# quadESP_Mark_2.net
KiCad netlist of a schematic drawn in EAGLE
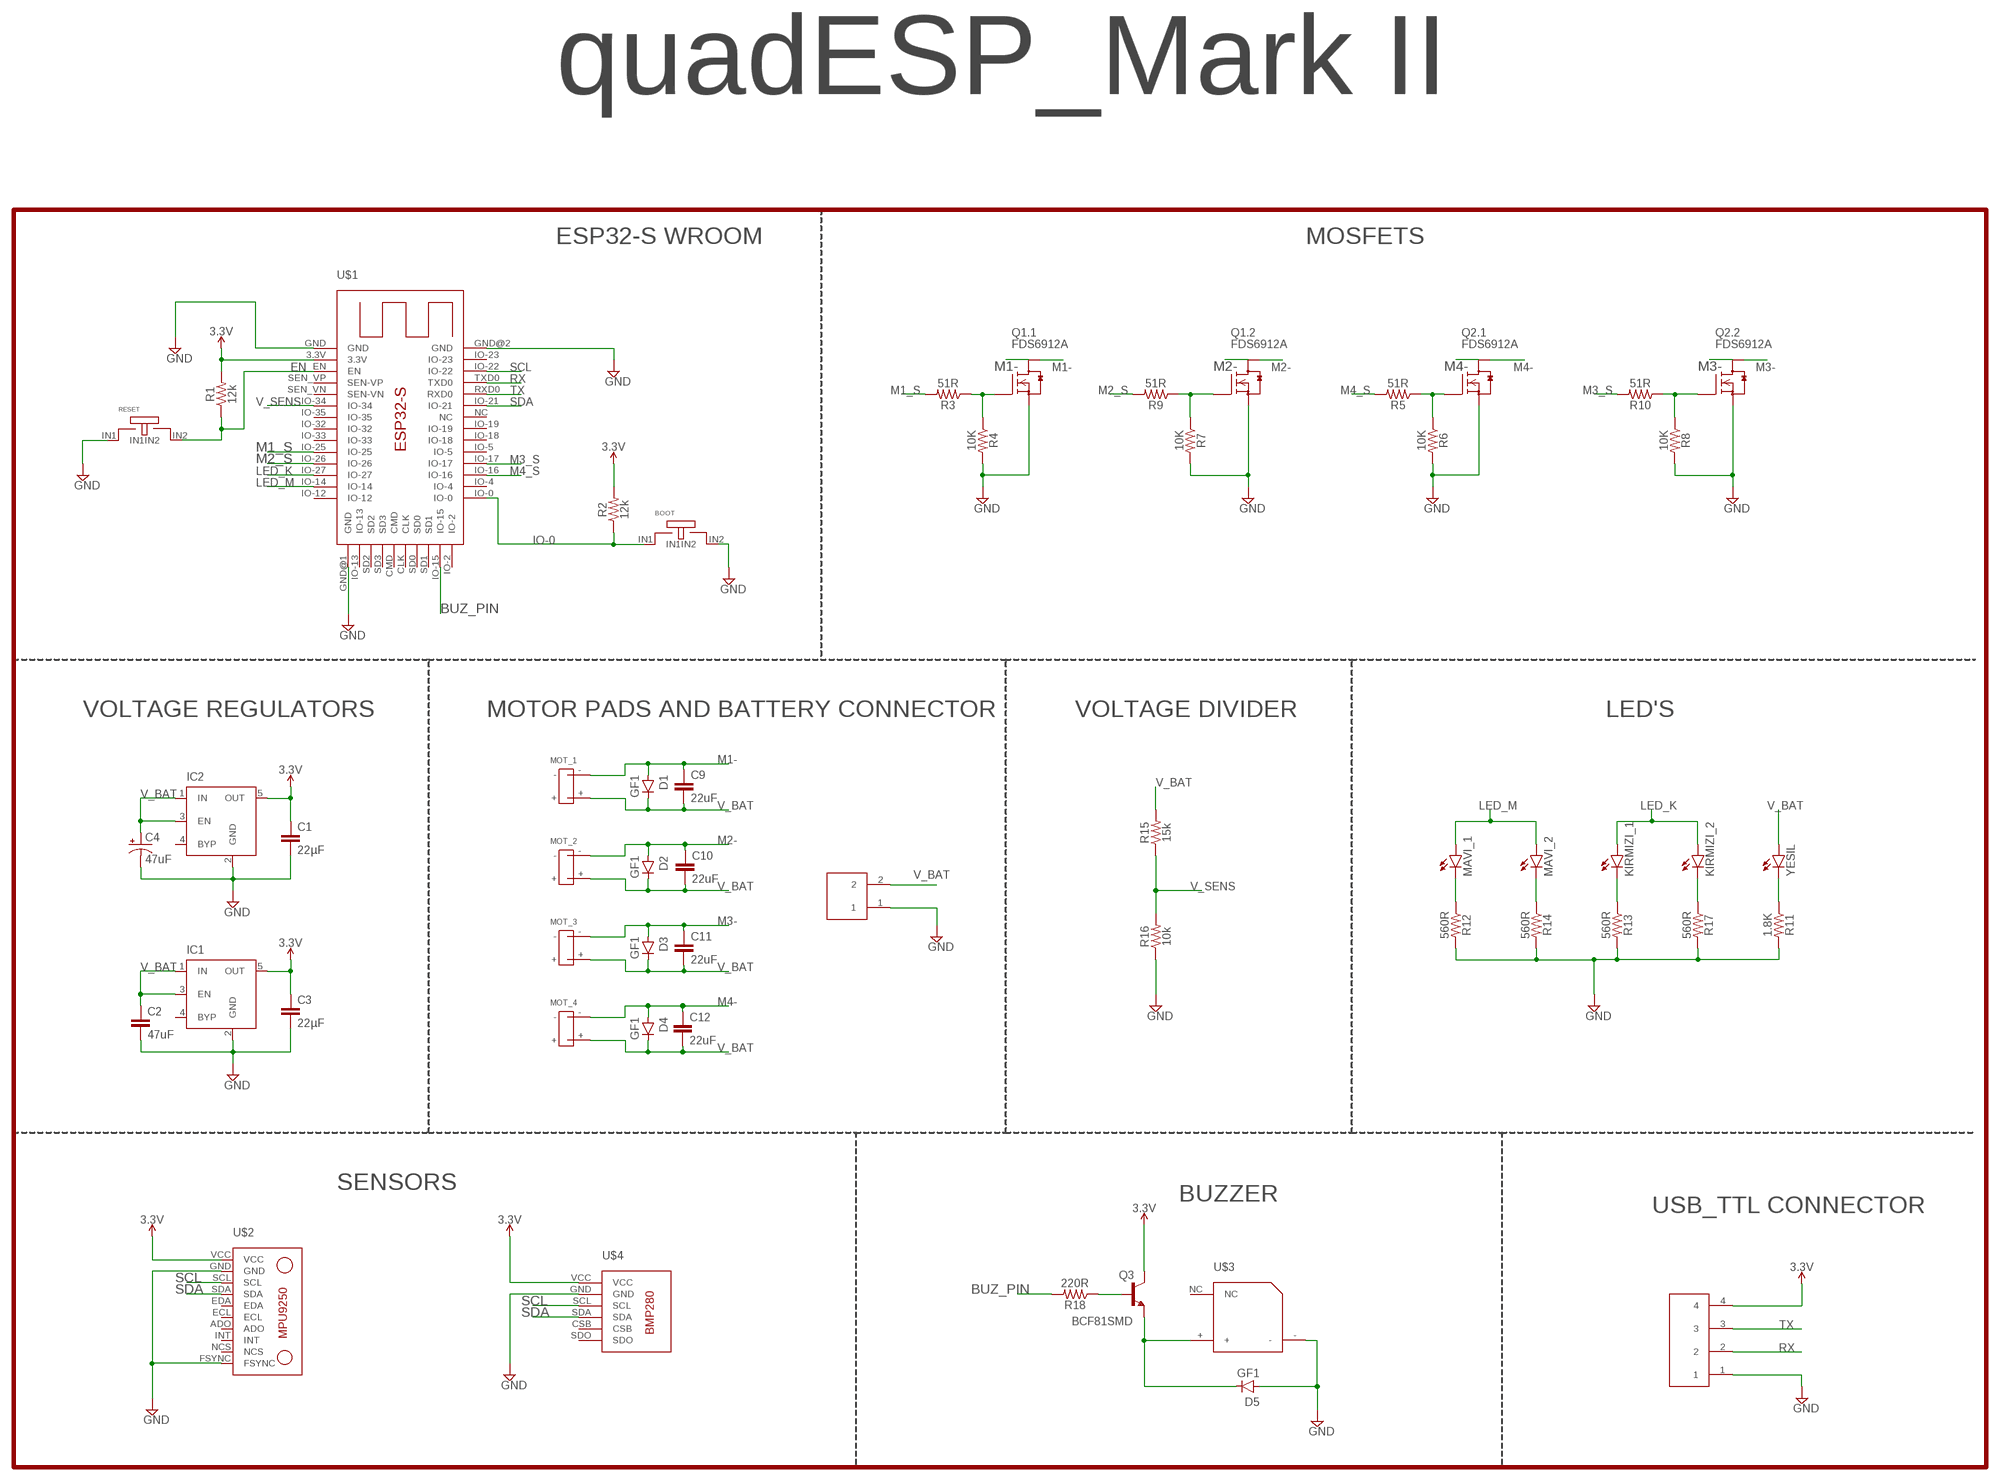
[diagram p0: schematic, sheet 1]

(export (version "E")
  (design (tool "Eeschema 10.0.6"))
  (components
    (comp (ref "BOOT")
      (value "MINI_TIP_SMD_TACT_SWITCH_BUTON")
      (footprint "eagle-import:MINI_TIP_SMD_TACT_SWITCH_BUTON")
      (libsource (lib "eagle-import") (part "MINI_TIP_SMD_TACT_SWITCH_BUTON"))
    )
    (comp (ref "C1")
      (value "22µF")
      (footprint "eagle-import:0805")
      (libsource (lib "eagle-import") (part "0.33UF/330NF-0805-50V-10%"))
    )
    (comp (ref "C2")
      (value "47uF")
      (footprint "eagle-import:1206")
      (libsource (lib "eagle-import") (part "2.2UF-1206-50V-10%"))
    )
    (comp (ref "C3")
      (value "22µF")
      (footprint "eagle-import:0805")
      (libsource (lib "eagle-import") (part "0.33UF/330NF-0805-50V-10%"))
    )
    (comp (ref "C4")
      (value "47uF")
      (footprint "eagle-import:EIA3528")
      (libsource (lib "eagle-import") (part "47UF-POLAR-EIA3528-10V-10%"))
    )
    (comp (ref "C9")
      (value "22uF")
      (footprint "eagle-import:1206")
      (libsource (lib "eagle-import") (part "2.2UF-1206-50V-10%"))
    )
    (comp (ref "C10")
      (value "22uF")
      (footprint "eagle-import:1206")
      (libsource (lib "eagle-import") (part "2.2UF-1206-50V-10%"))
    )
    (comp (ref "C11")
      (value "22uF")
      (footprint "eagle-import:1206")
      (libsource (lib "eagle-import") (part "2.2UF-1206-50V-10%"))
    )
    (comp (ref "C12")
      (value "22uF")
      (footprint "eagle-import:1206")
      (libsource (lib "eagle-import") (part "2.2UF-1206-50V-10%"))
    )
    (comp (ref "D1")
      (value "GF1")
      (footprint "eagle-import:SMA-DO214AC")
      (libsource (lib "eagle-import") (part "GF1"))
    )
    (comp (ref "D2")
      (value "GF1")
      (footprint "eagle-import:SMA-DO214AC")
      (libsource (lib "eagle-import") (part "GF1"))
    )
    (comp (ref "D3")
      (value "GF1")
      (footprint "eagle-import:SMA-DO214AC")
      (libsource (lib "eagle-import") (part "GF1"))
    )
    (comp (ref "D4")
      (value "GF1")
      (footprint "eagle-import:SMA-DO214AC")
      (libsource (lib "eagle-import") (part "GF1"))
    )
    (comp (ref "D5")
      (value "GF1")
      (footprint "eagle-import:SMA-DO214AC")
      (libsource (lib "eagle-import") (part "GF1"))
    )
    (comp (ref "IC1")
      (value "MIC5219XX")
      (footprint "eagle-import:SOT23-5")
      (libsource (lib "eagle-import") (part "MIC5219XX"))
    )
    (comp (ref "IC2")
      (value "MIC5219XX")
      (footprint "eagle-import:SOT23-5")
      (libsource (lib "eagle-import") (part "MIC5219XX"))
    )
    (comp (ref "KIRMIZI_1")
      (value "LEDCHIP-LED0805")
      (footprint "eagle-import:CHIP-LED0805")
      (libsource (lib "eagle-import") (part "LEDCHIP-LED0805"))
    )
    (comp (ref "KIRMIZI_2")
      (value "LEDCHIP-LED0805")
      (footprint "eagle-import:CHIP-LED0805")
      (libsource (lib "eagle-import") (part "LEDCHIP-LED0805"))
    )
    (comp (ref "MAVI_1")
      (value "LEDCHIP-LED0805")
      (footprint "eagle-import:CHIP-LED0805")
      (libsource (lib "eagle-import") (part "LEDCHIP-LED0805"))
    )
    (comp (ref "MAVI_2")
      (value "LEDCHIP-LED0805")
      (footprint "eagle-import:CHIP-LED0805")
      (libsource (lib "eagle-import") (part "LEDCHIP-LED0805"))
    )
    (comp (ref "MOT_1")
      (value "2X_SOLDER_PAD")
      (footprint "eagle-import:2X_SOLDER_PAD")
      (libsource (lib "eagle-import") (part "2X_SOLDER_PAD"))
    )
    (comp (ref "MOT_2")
      (value "2X_SOLDER_PAD")
      (footprint "eagle-import:2X_SOLDER_PAD")
      (libsource (lib "eagle-import") (part "2X_SOLDER_PAD"))
    )
    (comp (ref "MOT_3")
      (value "2X_SOLDER_PAD")
      (footprint "eagle-import:2X_SOLDER_PAD")
      (libsource (lib "eagle-import") (part "2X_SOLDER_PAD"))
    )
    (comp (ref "MOT_4")
      (value "2X_SOLDER_PAD")
      (footprint "eagle-import:2X_SOLDER_PAD")
      (libsource (lib "eagle-import") (part "2X_SOLDER_PAD"))
    )
    (comp (ref "Q1")
      (value "FDS6912A")
      (footprint "eagle-import:SO-8")
      (libsource (lib "eagle-import") (part "FDS6912A"))
    )
    (comp (ref "Q2")
      (value "FDS6912A")
      (footprint "eagle-import:SO-8")
      (libsource (lib "eagle-import") (part "FDS6912A"))
    )
    (comp (ref "Q3")
      (value "BCF81SMD")
      (footprint "eagle-import:SOT23-BEC")
      (libsource (lib "eagle-import") (part "BCF81SMD"))
    )
    (comp (ref "R1")
      (value "12k")
      (footprint "eagle-import:0805")
      (libsource (lib "eagle-import") (part "0.3OHM-0805-1/8W-1%"))
    )
    (comp (ref "R2")
      (value "12k")
      (footprint "eagle-import:0805")
      (libsource (lib "eagle-import") (part "0.3OHM-0805-1/8W-1%"))
    )
    (comp (ref "R3")
      (value "51R")
      (footprint "eagle-import:0805")
      (libsource (lib "eagle-import") (part "0.3OHM-0805-1/8W-1%"))
    )
    (comp (ref "R4")
      (value "10K")
      (footprint "eagle-import:0805")
      (libsource (lib "eagle-import") (part "0.3OHM-0805-1/8W-1%"))
    )
    (comp (ref "R5")
      (value "51R")
      (footprint "eagle-import:0805")
      (libsource (lib "eagle-import") (part "0.3OHM-0805-1/8W-1%"))
    )
    (comp (ref "R6")
      (value "10K")
      (footprint "eagle-import:0805")
      (libsource (lib "eagle-import") (part "0.3OHM-0805-1/8W-1%"))
    )
    (comp (ref "R7")
      (value "10K")
      (footprint "eagle-import:0805")
      (libsource (lib "eagle-import") (part "0.3OHM-0805-1/8W-1%"))
    )
    (comp (ref "R8")
      (value "10K")
      (footprint "eagle-import:0805")
      (libsource (lib "eagle-import") (part "0.3OHM-0805-1/8W-1%"))
    )
    (comp (ref "R9")
      (value "51R")
      (footprint "eagle-import:0805")
      (libsource (lib "eagle-import") (part "0.3OHM-0805-1/8W-1%"))
    )
    (comp (ref "R10")
      (value "51R")
      (footprint "eagle-import:0805")
      (libsource (lib "eagle-import") (part "0.3OHM-0805-1/8W-1%"))
    )
    (comp (ref "R11")
      (value "1.8K")
      (footprint "eagle-import:0805")
      (libsource (lib "eagle-import") (part "0.3OHM-0805-1/8W-1%"))
    )
    (comp (ref "R12")
      (value "560R")
      (footprint "eagle-import:0805")
      (libsource (lib "eagle-import") (part "0.3OHM-0805-1/8W-1%"))
    )
    (comp (ref "R13")
      (value "560R")
      (footprint "eagle-import:0805")
      (libsource (lib "eagle-import") (part "0.3OHM-0805-1/8W-1%"))
    )
    (comp (ref "R14")
      (value "560R")
      (footprint "eagle-import:0805")
      (libsource (lib "eagle-import") (part "0.3OHM-0805-1/8W-1%"))
    )
    (comp (ref "R15")
      (value "15k")
      (footprint "eagle-import:0805")
      (libsource (lib "eagle-import") (part "0.3OHM-0805-1/8W-1%"))
    )
    (comp (ref "R16")
      (value "10k")
      (footprint "eagle-import:0805")
      (libsource (lib "eagle-import") (part "0.3OHM-0805-1/8W-1%"))
    )
    (comp (ref "R17")
      (value "560R")
      (footprint "eagle-import:0805")
      (libsource (lib "eagle-import") (part "0.3OHM-0805-1/8W-1%"))
    )
    (comp (ref "R18")
      (value "220R")
      (footprint "eagle-import:0805")
      (libsource (lib "eagle-import") (part "0.3OHM-0805-1/8W-1%"))
    )
    (comp (ref "RESET")
      (value "MINI_TIP_SMD_TACT_SWITCH_BUTON")
      (footprint "eagle-import:MINI_TIP_SMD_TACT_SWITCH_BUTON")
      (libsource (lib "eagle-import") (part "MINI_TIP_SMD_TACT_SWITCH_BUTON"))
    )
    (comp (ref "U$1")
      (value "ESP32-S")
      (footprint "eagle-import:ESP32-S")
      (libsource (lib "eagle-import") (part "ESP32-S"))
    )
    (comp (ref "U$2")
      (value "MPU9250")
      (footprint "eagle-import:MPU9250")
      (libsource (lib "eagle-import") (part "MPU9250"))
    )
    (comp (ref "U$3")
      (value "PASIVE_BUZZER_5MM_X_5MM_20MM")
      (footprint "eagle-import:PASIVE_BUZZER_5MM_X_5MM_20MM")
      (libsource (lib "eagle-import") (part "PASIVE_BUZZER_5MM_X_5MM_20MM"))
    )
    (comp (ref "U$4")
      (value "BMP280")
      (footprint "eagle-import:BMP280")
      (libsource (lib "eagle-import") (part "BMP280"))
    )
    (comp (ref "U$5")
      (value "2_PIN_TUNIC")
      (footprint "eagle-import:2_PIN_TUNIC")
      (libsource (lib "eagle-import") (part "2_PIN_TUNIC"))
    )
    (comp (ref "U$6")
      (value "4_PIN_TUNIC")
      (footprint "eagle-import:4_PIN_TUNIC")
      (libsource (lib "eagle-import") (part "4_PIN_TUNIC"))
    )
    (comp (ref "YESIL")
      (value "LEDCHIP-LED0805")
      (footprint "eagle-import:CHIP-LED0805")
      (libsource (lib "eagle-import") (part "LEDCHIP-LED0805"))
    )
  )
  (nets
    (net (code "1") (name "/BUZ_PIN") (class "Default")
      (node (ref "R18") (pin "2") (pinfunction "2_2") (pintype "passive"))
      (node (ref "U$1") (pin "IO-15") (pinfunction "IO-15_IO-15") (pintype "bidirectional"))
    )
    (net (code "2") (name "/EN") (class "Default")
      (node (ref "R1") (pin "1") (pinfunction "1_1") (pintype "passive"))
      (node (ref "RESET") (pin "IN2") (pinfunction "IN2_IN2") (pintype "bidirectional"))
      (node (ref "U$1") (pin "EN") (pinfunction "EN_EN") (pintype "bidirectional"))
    )
    (net (code "3") (name "/IO-0") (class "Default")
      (node (ref "BOOT") (pin "IN1") (pinfunction "IN1_IN1") (pintype "bidirectional"))
      (node (ref "R2") (pin "1") (pinfunction "1_1") (pintype "passive"))
      (node (ref "U$1") (pin "IO-0") (pinfunction "IO-0_IO-0") (pintype "bidirectional"))
    )
    (net (code "4") (name "/LED_K") (class "Default")
      (node (ref "KIRMIZI_1") (pin "A") (pinfunction "A_A") (pintype "passive"))
      (node (ref "KIRMIZI_2") (pin "A") (pinfunction "A_A") (pintype "passive"))
      (node (ref "U$1") (pin "IO-27") (pinfunction "IO-27_IO-27") (pintype "bidirectional"))
    )
    (net (code "5") (name "/LED_M") (class "Default")
      (node (ref "MAVI_1") (pin "A") (pinfunction "A_A") (pintype "passive"))
      (node (ref "MAVI_2") (pin "A") (pinfunction "A_A") (pintype "passive"))
      (node (ref "U$1") (pin "IO-14") (pinfunction "IO-14_IO-14") (pintype "bidirectional"))
    )
    (net (code "6") (name "/M1-") (class "Default")
      (node (ref "C9") (pin "1") (pinfunction "1_1") (pintype "passive"))
      (node (ref "D1") (pin "A") (pinfunction "A_A") (pintype "passive"))
      (node (ref "MOT_1") (pin "-") (pinfunction "-_-") (pintype "bidirectional"))
      (node (ref "Q1") (pin "5") (pinfunction "D_5") (pintype "passive"))
      (node (ref "Q1") (pin "6") (pinfunction "D_6") (pintype "passive"))
    )
    (net (code "7") (name "/M1_S") (class "Default")
      (node (ref "R3") (pin "2") (pinfunction "2_2") (pintype "passive"))
      (node (ref "U$1") (pin "IO-25") (pinfunction "IO-25_IO-25") (pintype "bidirectional"))
    )
    (net (code "8") (name "/M2-") (class "Default")
      (node (ref "C10") (pin "1") (pinfunction "1_1") (pintype "passive"))
      (node (ref "D2") (pin "A") (pinfunction "A_A") (pintype "passive"))
      (node (ref "MOT_2") (pin "-") (pinfunction "-_-") (pintype "bidirectional"))
      (node (ref "Q1") (pin "7") (pinfunction "D_7") (pintype "passive"))
      (node (ref "Q1") (pin "8") (pinfunction "D_8") (pintype "passive"))
    )
    (net (code "9") (name "/M2_S") (class "Default")
      (node (ref "R9") (pin "2") (pinfunction "2_2") (pintype "passive"))
      (node (ref "U$1") (pin "IO-26") (pinfunction "IO-26_IO-26") (pintype "bidirectional"))
    )
    (net (code "10") (name "/M3-") (class "Default")
      (node (ref "C11") (pin "1") (pinfunction "1_1") (pintype "passive"))
      (node (ref "D3") (pin "A") (pinfunction "A_A") (pintype "passive"))
      (node (ref "MOT_3") (pin "-") (pinfunction "-_-") (pintype "bidirectional"))
      (node (ref "Q2") (pin "7") (pinfunction "D_7") (pintype "passive"))
      (node (ref "Q2") (pin "8") (pinfunction "D_8") (pintype "passive"))
    )
    (net (code "11") (name "/M3_S") (class "Default")
      (node (ref "R10") (pin "2") (pinfunction "2_2") (pintype "passive"))
      (node (ref "U$1") (pin "IO-17") (pinfunction "IO-17_IO-17") (pintype "bidirectional"))
    )
    (net (code "12") (name "/M4-") (class "Default")
      (node (ref "C12") (pin "1") (pinfunction "1_1") (pintype "passive"))
      (node (ref "D4") (pin "A") (pinfunction "A_A") (pintype "passive"))
      (node (ref "MOT_4") (pin "-") (pinfunction "-_-") (pintype "bidirectional"))
      (node (ref "Q2") (pin "5") (pinfunction "D_5") (pintype "passive"))
      (node (ref "Q2") (pin "6") (pinfunction "D_6") (pintype "passive"))
    )
    (net (code "13") (name "/M4_S") (class "Default")
      (node (ref "R5") (pin "2") (pinfunction "2_2") (pintype "passive"))
      (node (ref "U$1") (pin "IO-16") (pinfunction "IO-16_IO-16") (pintype "bidirectional"))
    )
    (net (code "14") (name "/RX") (class "Default")
      (node (ref "U$1") (pin "TXD0") (pinfunction "TXD0_TXD0") (pintype "bidirectional"))
      (node (ref "U$6") (pin "2") (pinfunction "2_2") (pintype "bidirectional"))
    )
    (net (code "15") (name "/SCL") (class "Default")
      (node (ref "U$1") (pin "IO-22") (pinfunction "IO-22_IO-22") (pintype "bidirectional"))
      (node (ref "U$2") (pin "SCL") (pinfunction "SCL_SCL") (pintype "bidirectional"))
      (node (ref "U$4") (pin "SCL") (pinfunction "SCL_SCL") (pintype "bidirectional"))
    )
    (net (code "16") (name "/SDA") (class "Default")
      (node (ref "U$1") (pin "IO-21") (pinfunction "IO-21_IO-21") (pintype "bidirectional"))
      (node (ref "U$2") (pin "SDA") (pinfunction "SDA_SDA") (pintype "bidirectional"))
      (node (ref "U$4") (pin "SDA") (pinfunction "SDA_SDA") (pintype "bidirectional"))
    )
    (net (code "17") (name "/TX") (class "Default")
      (node (ref "U$1") (pin "RXD0") (pinfunction "RXD0_RXD0") (pintype "bidirectional"))
      (node (ref "U$6") (pin "3") (pinfunction "3_3") (pintype "bidirectional"))
    )
    (net (code "18") (name "/V_BAT") (class "Default")
      (node (ref "C10") (pin "2") (pinfunction "2_2") (pintype "passive"))
      (node (ref "C11") (pin "2") (pinfunction "2_2") (pintype "passive"))
      (node (ref "C12") (pin "2") (pinfunction "2_2") (pintype "passive"))
      (node (ref "C2") (pin "1") (pinfunction "1_1") (pintype "passive"))
      (node (ref "C4") (pin "A") (pinfunction "+_A") (pintype "passive"))
      (node (ref "C9") (pin "2") (pinfunction "2_2") (pintype "passive"))
      (node (ref "D1") (pin "K") (pinfunction "C_K") (pintype "passive"))
      (node (ref "D2") (pin "K") (pinfunction "C_K") (pintype "passive"))
      (node (ref "D3") (pin "K") (pinfunction "C_K") (pintype "passive"))
      (node (ref "D4") (pin "K") (pinfunction "C_K") (pintype "passive"))
      (node (ref "IC1") (pin "1") (pinfunction "IN_1") (pintype "input"))
      (node (ref "IC1") (pin "3") (pinfunction "EN_3") (pintype "input"))
      (node (ref "IC2") (pin "1") (pinfunction "IN_1") (pintype "input"))
      (node (ref "IC2") (pin "3") (pinfunction "EN_3") (pintype "input"))
      (node (ref "MOT_1") (pin "+") (pinfunction "+_+") (pintype "bidirectional"))
      (node (ref "MOT_2") (pin "+") (pinfunction "+_+") (pintype "bidirectional"))
      (node (ref "MOT_3") (pin "+") (pinfunction "+_+") (pintype "bidirectional"))
      (node (ref "MOT_4") (pin "+") (pinfunction "+_+") (pintype "bidirectional"))
      (node (ref "R15") (pin "2") (pinfunction "2_2") (pintype "passive"))
      (node (ref "U$5") (pin "2") (pinfunction "2_2") (pintype "bidirectional"))
      (node (ref "YESIL") (pin "A") (pinfunction "A_A") (pintype "passive"))
    )
    (net (code "19") (name "/V_SENS") (class "Default")
      (node (ref "R15") (pin "1") (pinfunction "1_1") (pintype "passive"))
      (node (ref "R16") (pin "2") (pinfunction "2_2") (pintype "passive"))
      (node (ref "U$1") (pin "IO-34") (pinfunction "IO-34_IO-34") (pintype "bidirectional"))
    )
    (net (code "20") (name "3.3V") (class "Default")
      (node (ref "C1") (pin "1") (pinfunction "1_1") (pintype "passive"))
      (node (ref "C3") (pin "1") (pinfunction "1_1") (pintype "passive"))
      (node (ref "IC1") (pin "5") (pinfunction "OUT_5") (pintype "output"))
      (node (ref "IC2") (pin "5") (pinfunction "OUT_5") (pintype "output"))
      (node (ref "Q3") (pin "C") (pinfunction "C_C") (pintype "passive"))
      (node (ref "R1") (pin "2") (pinfunction "2_2") (pintype "passive"))
      (node (ref "R2") (pin "2") (pinfunction "2_2") (pintype "passive"))
      (node (ref "U$1") (pin "3.3V") (pinfunction "3.3V_3.3V") (pintype "bidirectional"))
      (node (ref "U$2") (pin "VCC") (pinfunction "VCC_VCC") (pintype "bidirectional"))
      (node (ref "U$4") (pin "VCC") (pinfunction "VCC_VCC") (pintype "bidirectional"))
      (node (ref "U$6") (pin "4") (pinfunction "4_4") (pintype "bidirectional"))
    )
    (net (code "21") (name "GND") (class "Default")
      (node (ref "BOOT") (pin "IN2") (pinfunction "IN2_IN2") (pintype "bidirectional"))
      (node (ref "C1") (pin "2") (pinfunction "2_2") (pintype "passive"))
      (node (ref "C2") (pin "2") (pinfunction "2_2") (pintype "passive"))
      (node (ref "C3") (pin "2") (pinfunction "2_2") (pintype "passive"))
      (node (ref "C4") (pin "C") (pinfunction "-_C") (pintype "passive"))
      (node (ref "D5") (pin "A") (pinfunction "A_A") (pintype "passive"))
      (node (ref "IC1") (pin "2") (pinfunction "GND_2") (pintype "power_in"))
      (node (ref "IC2") (pin "2") (pinfunction "GND_2") (pintype "power_in"))
      (node (ref "Q1") (pin "1") (pinfunction "S_1") (pintype "passive"))
      (node (ref "Q1") (pin "3") (pinfunction "S_3") (pintype "passive"))
      (node (ref "Q2") (pin "1") (pinfunction "S_1") (pintype "passive"))
      (node (ref "Q2") (pin "3") (pinfunction "S_3") (pintype "passive"))
      (node (ref "R11") (pin "2") (pinfunction "2_2") (pintype "passive"))
      (node (ref "R12") (pin "2") (pinfunction "2_2") (pintype "passive"))
      (node (ref "R13") (pin "2") (pinfunction "2_2") (pintype "passive"))
      (node (ref "R14") (pin "2") (pinfunction "2_2") (pintype "passive"))
      (node (ref "R16") (pin "1") (pinfunction "1_1") (pintype "passive"))
      (node (ref "R17") (pin "2") (pinfunction "2_2") (pintype "passive"))
      (node (ref "R4") (pin "2") (pinfunction "2_2") (pintype "passive"))
      (node (ref "R6") (pin "2") (pinfunction "2_2") (pintype "passive"))
      (node (ref "R7") (pin "2") (pinfunction "2_2") (pintype "passive"))
      (node (ref "R8") (pin "2") (pinfunction "2_2") (pintype "passive"))
      (node (ref "RESET") (pin "IN1") (pinfunction "IN1_IN1") (pintype "bidirectional"))
      (node (ref "U$1") (pin "GND") (pinfunction "GND_GND") (pintype "bidirectional"))
      (node (ref "U$1") (pin "GND@1") (pinfunction "GND_GND@1") (pintype "bidirectional"))
      (node (ref "U$1") (pin "GND@2") (pinfunction "GND_GND@2") (pintype "bidirectional"))
      (node (ref "U$2") (pin "FSYNC") (pinfunction "FSYNC_FSYNC") (pintype "bidirectional"))
      (node (ref "U$2") (pin "GND") (pinfunction "GND_GND") (pintype "bidirectional"))
      (node (ref "U$3") (pin "-") (pinfunction "-_-") (pintype "bidirectional"))
      (node (ref "U$4") (pin "GND") (pinfunction "GND_GND") (pintype "bidirectional"))
      (node (ref "U$5") (pin "1") (pinfunction "1_1") (pintype "bidirectional"))
      (node (ref "U$6") (pin "1") (pinfunction "1_1") (pintype "bidirectional"))
    )
    (net (code "22") (name "Net-(D5-C)") (class "Default")
      (node (ref "D5") (pin "K") (pinfunction "C_K") (pintype "passive"))
      (node (ref "Q3") (pin "E") (pinfunction "E_E") (pintype "passive"))
      (node (ref "U$3") (pin "+") (pinfunction "+_+") (pintype "bidirectional"))
    )
    (net (code "23") (name "Net-(KIRMIZI_1-PadC)") (class "Default")
      (node (ref "KIRMIZI_1") (pin "C") (pinfunction "C_C") (pintype "passive"))
      (node (ref "R13") (pin "1") (pinfunction "1_1") (pintype "passive"))
    )
    (net (code "24") (name "Net-(KIRMIZI_2-PadC)") (class "Default")
      (node (ref "KIRMIZI_2") (pin "C") (pinfunction "C_C") (pintype "passive"))
      (node (ref "R17") (pin "1") (pinfunction "1_1") (pintype "passive"))
    )
    (net (code "25") (name "Net-(MAVI_1-PadC)") (class "Default")
      (node (ref "MAVI_1") (pin "C") (pinfunction "C_C") (pintype "passive"))
      (node (ref "R12") (pin "1") (pinfunction "1_1") (pintype "passive"))
    )
    (net (code "26") (name "Net-(MAVI_2-PadC)") (class "Default")
      (node (ref "MAVI_2") (pin "C") (pinfunction "C_C") (pintype "passive"))
      (node (ref "R14") (pin "1") (pinfunction "1_1") (pintype "passive"))
    )
    (net (code "27") (name "Net-(Q1A-G)") (class "Default")
      (node (ref "Q1") (pin "4") (pinfunction "G_4") (pintype "passive"))
      (node (ref "R3") (pin "1") (pinfunction "1_1") (pintype "passive"))
      (node (ref "R4") (pin "1") (pinfunction "1_1") (pintype "passive"))
    )
    (net (code "28") (name "Net-(Q1B-G)") (class "Default")
      (node (ref "Q1") (pin "2") (pinfunction "G_2") (pintype "passive"))
      (node (ref "R7") (pin "1") (pinfunction "1_1") (pintype "passive"))
      (node (ref "R9") (pin "1") (pinfunction "1_1") (pintype "passive"))
    )
    (net (code "29") (name "Net-(Q2A-G)") (class "Default")
      (node (ref "Q2") (pin "4") (pinfunction "G_4") (pintype "passive"))
      (node (ref "R5") (pin "1") (pinfunction "1_1") (pintype "passive"))
      (node (ref "R6") (pin "1") (pinfunction "1_1") (pintype "passive"))
    )
    (net (code "30") (name "Net-(Q2B-G)") (class "Default")
      (node (ref "Q2") (pin "2") (pinfunction "G_2") (pintype "passive"))
      (node (ref "R10") (pin "1") (pinfunction "1_1") (pintype "passive"))
      (node (ref "R8") (pin "1") (pinfunction "1_1") (pintype "passive"))
    )
    (net (code "31") (name "Net-(Q3-PadB)") (class "Default")
      (node (ref "Q3") (pin "B") (pinfunction "B_B") (pintype "passive"))
      (node (ref "R18") (pin "1") (pinfunction "1_1") (pintype "passive"))
    )
    (net (code "32") (name "Net-(R11-Pad1)") (class "Default")
      (node (ref "R11") (pin "1") (pinfunction "1_1") (pintype "passive"))
      (node (ref "YESIL") (pin "C") (pinfunction "C_C") (pintype "passive"))
    )
    (net (code "33") (name "unconnected-(IC1-BYP-Pad4)") (class "Default")
      (node (ref "IC1") (pin "4") (pinfunction "BYP_4") (pintype "passive"))
    )
    (net (code "34") (name "unconnected-(IC2-BYP-Pad4)") (class "Default")
      (node (ref "IC2") (pin "4") (pinfunction "BYP_4") (pintype "passive"))
    )
    (net (code "35") (name "unconnected-(U$1-PadCLK)") (class "Default")
      (node (ref "U$1") (pin "CLK") (pinfunction "CLK_CLK") (pintype "bidirectional"))
    )
    (net (code "36") (name "unconnected-(U$1-PadCMD)") (class "Default")
      (node (ref "U$1") (pin "CMD") (pinfunction "CMD_CMD") (pintype "bidirectional"))
    )
    (net (code "37") (name "unconnected-(U$1-PadIO-2)") (class "Default")
      (node (ref "U$1") (pin "IO-2") (pinfunction "IO-2_IO-2") (pintype "bidirectional"))
    )
    (net (code "38") (name "unconnected-(U$1-PadIO-4)") (class "Default")
      (node (ref "U$1") (pin "IO-4") (pinfunction "IO-4_IO-4") (pintype "bidirectional"))
    )
    (net (code "39") (name "unconnected-(U$1-PadIO-5)") (class "Default")
      (node (ref "U$1") (pin "IO-5") (pinfunction "IO-5_IO-5") (pintype "bidirectional"))
    )
    (net (code "40") (name "unconnected-(U$1-PadIO-12)") (class "Default")
      (node (ref "U$1") (pin "IO-12") (pinfunction "IO-12_IO-12") (pintype "bidirectional"))
    )
    (net (code "41") (name "unconnected-(U$1-PadIO-13)") (class "Default")
      (node (ref "U$1") (pin "IO-13") (pinfunction "IO-13_IO-13") (pintype "bidirectional"))
    )
    (net (code "42") (name "unconnected-(U$1-PadIO-18)") (class "Default")
      (node (ref "U$1") (pin "IO-18") (pinfunction "IO-18_IO-18") (pintype "bidirectional"))
    )
    (net (code "43") (name "unconnected-(U$1-PadIO-19)") (class "Default")
      (node (ref "U$1") (pin "IO-19") (pinfunction "IO-19_IO-19") (pintype "bidirectional"))
    )
    (net (code "44") (name "unconnected-(U$1-PadIO-23)") (class "Default")
      (node (ref "U$1") (pin "IO-23") (pinfunction "IO-23_IO-23") (pintype "bidirectional"))
    )
    (net (code "45") (name "unconnected-(U$1-PadIO-32)") (class "Default")
      (node (ref "U$1") (pin "IO-32") (pinfunction "IO-32_IO-32") (pintype "bidirectional"))
    )
    (net (code "46") (name "unconnected-(U$1-PadIO-33)") (class "Default")
      (node (ref "U$1") (pin "IO-33") (pinfunction "IO-33_IO-33") (pintype "bidirectional"))
    )
    (net (code "47") (name "unconnected-(U$1-PadIO-35)") (class "Default")
      (node (ref "U$1") (pin "IO-35") (pinfunction "IO-35_IO-35") (pintype "bidirectional"))
    )
    (net (code "48") (name "unconnected-(U$1-PadNC)") (class "Default")
      (node (ref "U$1") (pin "NC") (pinfunction "NC_NC") (pintype "bidirectional"))
    )
    (net (code "49") (name "unconnected-(U$1-PadSD0)") (class "Default")
      (node (ref "U$1") (pin "SD0") (pinfunction "SD0_SD0") (pintype "bidirectional"))
    )
    (net (code "50") (name "unconnected-(U$1-PadSD1)") (class "Default")
      (node (ref "U$1") (pin "SD1") (pinfunction "SD1_SD1") (pintype "bidirectional"))
    )
    (net (code "51") (name "unconnected-(U$1-PadSD2)") (class "Default")
      (node (ref "U$1") (pin "SD2") (pinfunction "SD2_SD2") (pintype "bidirectional"))
    )
    (net (code "52") (name "unconnected-(U$1-PadSD3)") (class "Default")
      (node (ref "U$1") (pin "SD3") (pinfunction "SD3_SD3") (pintype "bidirectional"))
    )
    (net (code "53") (name "unconnected-(U$1-SEN-VN-PadSEN_VN)") (class "Default")
      (node (ref "U$1") (pin "SEN_VN") (pinfunction "SEN-VN_SEN_VN") (pintype "bidirectional"))
    )
    (net (code "54") (name "unconnected-(U$1-SEN-VP-PadSEN_VP)") (class "Default")
      (node (ref "U$1") (pin "SEN_VP") (pinfunction "SEN-VP_SEN_VP") (pintype "bidirectional"))
    )
    (net (code "55") (name "unconnected-(U$2-PadADO)") (class "Default")
      (node (ref "U$2") (pin "ADO") (pinfunction "ADO_ADO") (pintype "bidirectional"))
    )
    (net (code "56") (name "unconnected-(U$2-PadECL)") (class "Default")
      (node (ref "U$2") (pin "ECL") (pinfunction "ECL_ECL") (pintype "bidirectional"))
    )
    (net (code "57") (name "unconnected-(U$2-PadEDA)") (class "Default")
      (node (ref "U$2") (pin "EDA") (pinfunction "EDA_EDA") (pintype "bidirectional"))
    )
    (net (code "58") (name "unconnected-(U$2-PadINT)") (class "Default")
      (node (ref "U$2") (pin "INT") (pinfunction "INT_INT") (pintype "bidirectional"))
    )
    (net (code "59") (name "unconnected-(U$2-PadNCS)") (class "Default")
      (node (ref "U$2") (pin "NCS") (pinfunction "NCS_NCS") (pintype "bidirectional"))
    )
    (net (code "60") (name "unconnected-(U$3-PadNC)") (class "Default")
      (node (ref "U$3") (pin "NC") (pinfunction "NC_NC") (pintype "bidirectional"))
    )
    (net (code "61") (name "unconnected-(U$4-PadCSB)") (class "Default")
      (node (ref "U$4") (pin "CSB") (pinfunction "CSB_CSB") (pintype "bidirectional"))
    )
    (net (code "62") (name "unconnected-(U$4-PadSDO)") (class "Default")
      (node (ref "U$4") (pin "SDO") (pinfunction "SDO_SDO") (pintype "bidirectional"))
    )
  )
)
